# lightpowersupply.net
KiCad netlist of a schematic drawn in EAGLE
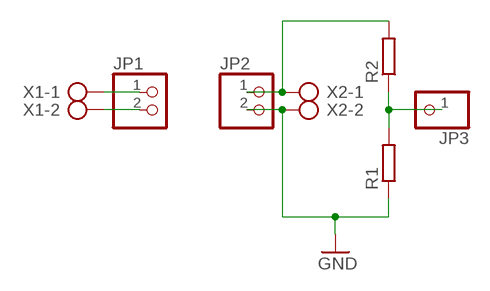
[diagram p0: schematic, sheet 1]

(export (version "E")
  (design (tool "Eeschema 10.0.6"))
  (components
    (comp (ref "JP1")
      (value "PINHD-1X2")
      (footprint "eagle-import:1X02")
      (libsource (lib "eagle-import") (part "PINHD-1X2"))
    )
    (comp (ref "JP2")
      (value "PINHD-1X2")
      (footprint "eagle-import:1X02")
      (libsource (lib "eagle-import") (part "PINHD-1X2"))
    )
    (comp (ref "JP3")
      (value "PINHD-1X1")
      (footprint "eagle-import:1X01")
      (libsource (lib "eagle-import") (part "PINHD-1X1"))
    )
    (comp (ref "R1")
      (value "R-EU_R1206")
      (footprint "eagle-import:R1206")
      (libsource (lib "eagle-import") (part "R-EU_R1206"))
    )
    (comp (ref "R2")
      (value "R-EU_R1206")
      (footprint "eagle-import:R1206")
      (libsource (lib "eagle-import") (part "R-EU_R1206"))
    )
    (comp (ref "X1")
      (value "AK300/2")
      (footprint "eagle-import:AK300_2")
      (libsource (lib "eagle-import") (part "AK300/2"))
    )
    (comp (ref "X2")
      (value "AK300/2")
      (footprint "eagle-import:AK300_2")
      (libsource (lib "eagle-import") (part "AK300/2"))
    )
  )
  (nets
    (net (code "1") (name "GND") (class "Default")
      (node (ref "JP2") (pin "2") (pinfunction "2_2") (pintype "passive"))
      (node (ref "R1") (pin "1") (pinfunction "1_1") (pintype "passive"))
      (node (ref "X2") (pin "2") (pinfunction "KL_2") (pintype "passive"))
    )
    (net (code "2") (name "Net-(JP3-Pad1)") (class "Default")
      (node (ref "JP3") (pin "1") (pinfunction "1_1") (pintype "passive"))
      (node (ref "R1") (pin "2") (pinfunction "2_2") (pintype "passive"))
      (node (ref "R2") (pin "1") (pinfunction "1_1") (pintype "passive"))
    )
    (net (code "3") (name "Net-(X1A-KL)") (class "Default")
      (node (ref "JP1") (pin "1") (pinfunction "1_1") (pintype "passive"))
      (node (ref "X1") (pin "1") (pinfunction "KL_1") (pintype "passive"))
    )
    (net (code "4") (name "Net-(X1B-KL)") (class "Default")
      (node (ref "JP1") (pin "2") (pinfunction "2_2") (pintype "passive"))
      (node (ref "X1") (pin "2") (pinfunction "KL_2") (pintype "passive"))
    )
    (net (code "5") (name "Net-(X2A-KL)") (class "Default")
      (node (ref "JP2") (pin "1") (pinfunction "1_1") (pintype "passive"))
      (node (ref "R2") (pin "2") (pinfunction "2_2") (pintype "passive"))
      (node (ref "X2") (pin "1") (pinfunction "KL_1") (pintype "passive"))
    )
  )
)
